# USB3_2_Type_A.net
KiCad netlist of a schematic drawn in Altium Designer
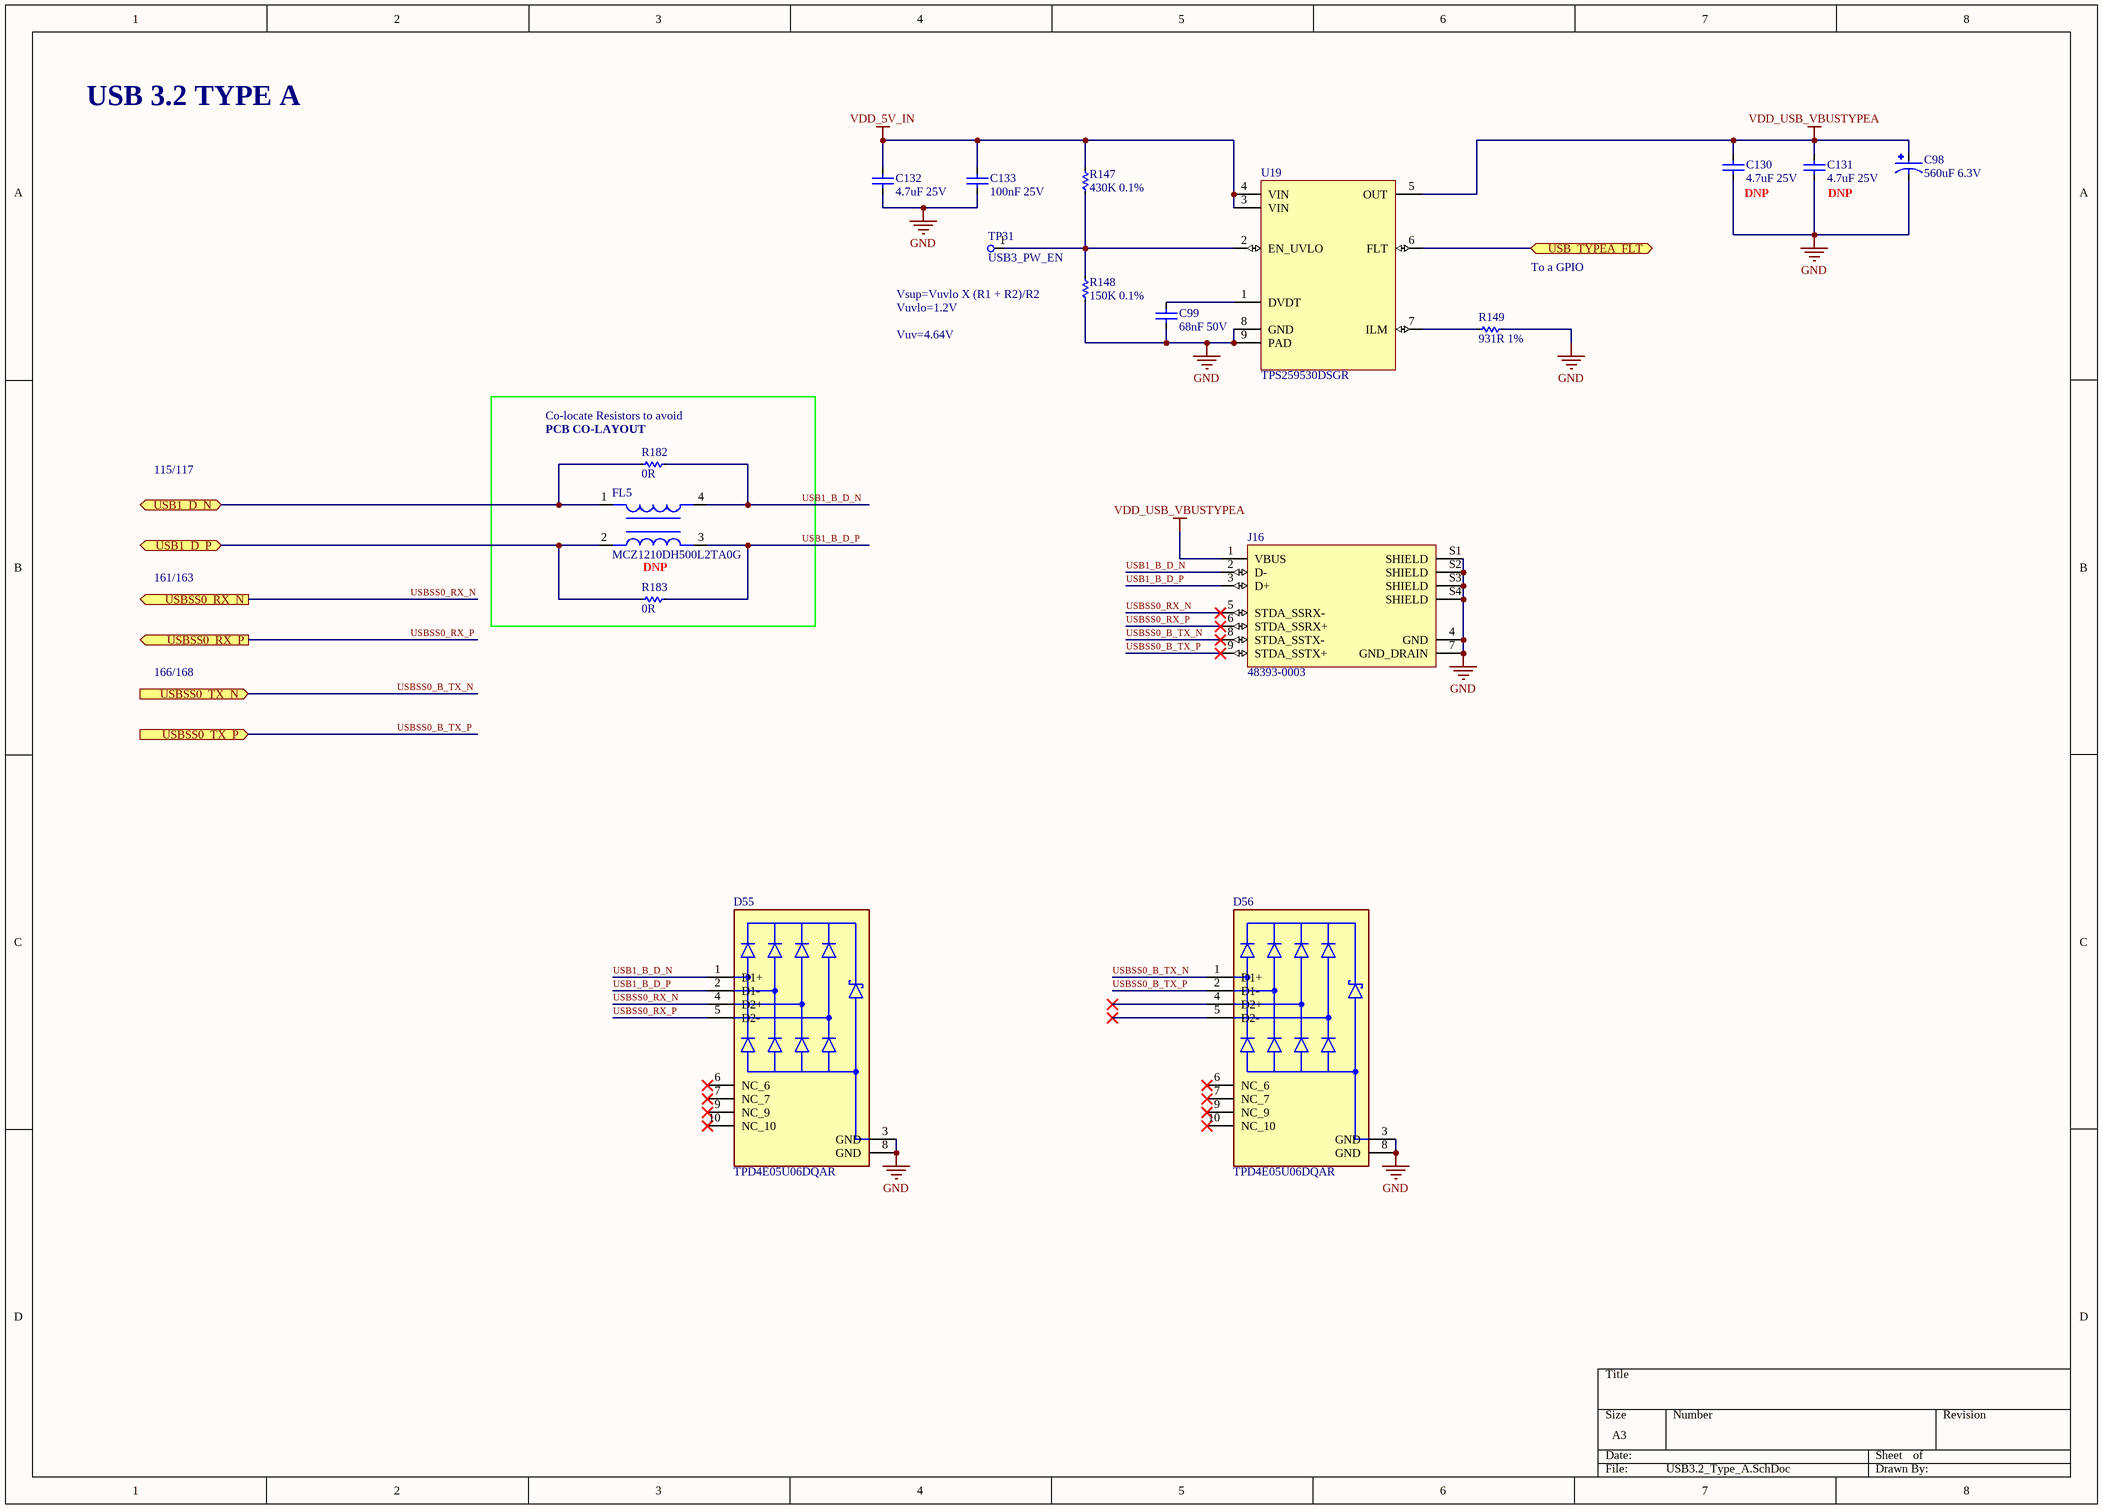
[diagram p0: USB3.2_Type_A.SchDoc]

(export (version "E")
  (design (tool "Eeschema 10.0.6"))
  (components
    (comp (ref "C98")
      (value "560uF 6.3V")
      (footprint "CP_ELEC_8X7.7")
      (description "Cap Aluminum Polymer 560uF 6.3VDC 20% (8 X 7.7mm) SMD 0.009 Ohm 4500mA 2000h 105C T/R")
      (fields
        (field (name "MANUFACTURER") "Nichicon")
        (field (name "MANUFACTURER PART NUMBER") "RHA0J561MCN1GS")
      )
      (libsource (lib "GM_Altium_Library") (part "RHA0J561MCN1GS"))
    )
    (comp (ref "C99")
      (value "68nF 50V")
      (footprint "C0805")
      (description "Cap Cer 0805 68NF 50V X7R 10%")
      (fields
        (field (name "MANUFACTURER") "KEMET")
        (field (name "MANUFACTURER PART NUMBER") "C0805C683K5RECAUTO7210")
      )
      (libsource (lib "GM_Altium_Library") (part "C0805C683K5RECAUTO7210"))
    )
    (comp (ref "C130")
      (value "4.7uF 25V")
      (footprint "C0603")
      (description "0603 4.7 uF 25 V ±10 % Tolerance X5R SMT Multilayer Ceramic Capacitor")
      (fields
        (field (name "MANUFACTURER") "Murata")
        (field (name "MANUFACTURER PART NUMBER") "GRM188R61E475KE11D")
      )
      (libsource (lib "GM_Altium_Library") (part "GRM188R61E475KE11D"))
    )
    (comp (ref "C131")
      (value "4.7uF 25V")
      (footprint "C0603")
      (description "0603 4.7 uF 25 V ±10 % Tolerance X5R SMT Multilayer Ceramic Capacitor")
      (fields
        (field (name "MANUFACTURER") "Murata")
        (field (name "MANUFACTURER PART NUMBER") "GRM188R61E475KE11D")
      )
      (libsource (lib "GM_Altium_Library") (part "GRM188R61E475KE11D"))
    )
    (comp (ref "C132")
      (value "4.7uF 25V")
      (footprint "C0603")
      (description "0603 4.7 uF 25 V ±10 % Tolerance X5R SMT Multilayer Ceramic Capacitor")
      (fields
        (field (name "MANUFACTURER") "Murata")
        (field (name "MANUFACTURER PART NUMBER") "GRM188R61E475KE11D")
      )
      (libsource (lib "GM_Altium_Library") (part "GRM188R61E475KE11D"))
    )
    (comp (ref "C133")
      (value "100nF 25V")
      (footprint "C0402")
      (description "CAP CER 0.1UF 25V X5R 0402 / High Value Multilayer Ceramic Capacitors (High dielectric type)")
      (fields
        (field (name "MANUFACTURER") "Taiyo Yuden")
        (field (name "MANUFACTURER PART NUMBER") "TMK105BJ104KV-F")
      )
      (libsource (lib "GM_Altium_Library") (part "TMK105BJ104KV-F"))
    )
    (comp (ref "D55")
      (value "TPD4E05U06DQAR")
      (footprint "TPD4E05U06DQAR")
      (description "Quad 0.5-pF, 5.5-V, ±12-kV ESD protection diode for USB, HDMI & High Speed Interfaces")
      (fields (field (name "MANUFACTURER") "Texas Instruments"))
      (libsource (lib "GM_Altium_Library") (part "TPD4E05U06DQAR"))
    )
    (comp (ref "D56")
      (value "TPD4E05U06DQAR")
      (footprint "TPD4E05U06DQAR")
      (description "Quad 0.5-pF, 5.5-V, ±12-kV ESD protection diode for USB, HDMI & High Speed Interfaces")
      (fields (field (name "MANUFACTURER") "Texas Instruments"))
      (libsource (lib "GM_Altium_Library") (part "TPD4E05U06DQAR"))
    )
    (comp (ref "FL5")
      (value "MCZ1210DH500L2TA0G")
      (footprint "MCZ1210DH500L2TA0G")
      (description "2 Line Common Mode Choke Surface Mount 50 Ohms 100mA DCR 2.5Ohm")
      (fields (field (name "MANUFACTURER") "TDK"))
      (libsource (lib "GM_Altium_Library") (part "MCZ1210DH500L2TA0G"))
    )
    (comp (ref "J16")
      (value "48393-0003")
      (footprint "0483930003")
      (description "Conn USB Type A F 9 POS 2mm/2.5mm Solder RA Thru-Hole 9 Terminal 1 Port Embossed T/R")
      (fields (field (name "MANUFACTURER") "Molex"))
      (libsource (lib "GM_Altium_Library") (part "48393-0003"))
    )
    (comp (ref "R147")
      (value "430K 0.1%")
      (footprint "R0603")
      (description "Res Thin Film 0603 430K Ohm 0.1% 1/16W ±25ppm/°C Molded SMD SMD Paper T/R")
      (fields
        (field (name "MANUFACTURER") "TE Connectivity")
        (field (name "MANUFACTURER PART NUMBER") "CPF0603B430KE1")
      )
      (libsource (lib "GM_Altium_Library") (part "CPF0603B430KE1"))
    )
    (comp (ref "R148")
      (value "150K 0.1%")
      (footprint "R0402")
      (description "Res Thin Film 0402 150K Ohm 0.1% 1/16W ±25ppm/°C Molded SMD")
      (fields
        (field (name "MANUFACTURER") "Yageo")
        (field (name "MANUFACTURER PART NUMBER") "RT0402BRD07150KL")
      )
      (libsource (lib "GM_Altium_Library") (part "RT0402BRD07150KL"))
    )
    (comp (ref "R149")
      (value "931R 1%")
      (footprint "R0402")
      (description "Res Thick Film 0402 931 Ohm 1% 1/16W ±100ppm/°C Molded SMD Paper T/R")
      (fields
        (field (name "MANUFACTURER") "Yageo")
        (field (name "MANUFACTURER PART NUMBER") "RC0402FR-07931RL")
      )
      (libsource (lib "GM_Altium_Library") (part "RC0402FR-07931RL"))
    )
    (comp (ref "R182")
      (value "0R")
      (footprint "R0402")
      (description "Res Jumper Thick Film 0402 0 Ohm 5% 1/16W Molded SMD Paper T/R")
      (fields
        (field (name "MANUFACTURER") "Yageo")
        (field (name "MANUFACTURER PART NUMBER") "RC0402JR-070RP")
      )
      (libsource (lib "GM_Altium_Library") (part "RC0402JR-070RP"))
    )
    (comp (ref "R183")
      (value "0R")
      (footprint "R0402")
      (description "Res Jumper Thick Film 0402 0 Ohm 5% 1/16W Molded SMD Paper T/R")
      (fields
        (field (name "MANUFACTURER") "Yageo")
        (field (name "MANUFACTURER PART NUMBER") "RC0402JR-070RP")
      )
      (libsource (lib "GM_Altium_Library") (part "RC0402JR-070RP"))
    )
    (comp (ref "TP31")
      (value "USB3_PW_EN")
      (footprint "TestPoint_Pad_D1.0mm")
      (libsource (lib "GM_Altium_Library") (part "TestPoint_D1mm"))
    )
    (comp (ref "U19")
      (value "TPS259530DSGR")
      (footprint "WSON(2X2)-8")
      (description "TPS259530 12V eFuse with Fast Overvoltage Protection 2.7V to 18V 4A 34m Ohm 8-Pin WSON T/R")
      (fields (field (name "MANUFACTURER") "Texas Instruments"))
      (libsource (lib "GM_Altium_Library") (part "TPS259530DSGR"))
    )
  )
  (nets
    (net (code "1") (name "/USB1_B_D_N") (class "Default")
      (node (ref "D55") (pin "1") (pinfunction "D1+_1") (pintype "passive"))
      (node (ref "FL5") (pin "4") (pinfunction "4_4") (pintype "passive"))
      (node (ref "J16") (pin "2") (pinfunction "D-_2") (pintype "bidirectional"))
      (node (ref "R182") (pin "2") (pinfunction "2_2") (pintype "passive"))
    )
    (net (code "2") (name "/USB1_B_D_P") (class "Default")
      (node (ref "D55") (pin "2") (pinfunction "D1-_2") (pintype "passive"))
      (node (ref "FL5") (pin "3") (pinfunction "3_3") (pintype "passive"))
      (node (ref "J16") (pin "3") (pinfunction "D+_3") (pintype "bidirectional"))
      (node (ref "R183") (pin "2") (pinfunction "2_2") (pintype "passive"))
    )
    (net (code "3") (name "/USB1_D_N") (class "Default")
      (node (ref "FL5") (pin "1") (pinfunction "1_1") (pintype "passive"))
      (node (ref "R182") (pin "1") (pinfunction "1_1") (pintype "passive"))
    )
    (net (code "4") (name "/USB1_D_P") (class "Default")
      (node (ref "FL5") (pin "2") (pinfunction "2_2") (pintype "passive"))
      (node (ref "R183") (pin "1") (pinfunction "1_1") (pintype "passive"))
    )
    (net (code "5") (name "/USBSS0_B_TX_N") (class "Default")
      (node (ref "D56") (pin "1") (pinfunction "D1+_1") (pintype "passive"))
      (node (ref "J16") (pin "8") (pinfunction "STDA_SSTX-_8") (pintype "bidirectional"))
    )
    (net (code "6") (name "/USBSS0_B_TX_P") (class "Default")
      (node (ref "D56") (pin "2") (pinfunction "D1-_2") (pintype "passive"))
      (node (ref "J16") (pin "9") (pinfunction "STDA_SSTX+_9") (pintype "bidirectional"))
    )
    (net (code "7") (name "/USBSS0_RX_N") (class "Default")
      (node (ref "D55") (pin "4") (pinfunction "D2+_4") (pintype "passive"))
      (node (ref "J16") (pin "5") (pinfunction "STDA_SSRX-_5") (pintype "bidirectional"))
    )
    (net (code "8") (name "/USBSS0_RX_P") (class "Default")
      (node (ref "D55") (pin "5") (pinfunction "D2-_5") (pintype "passive"))
      (node (ref "J16") (pin "6") (pinfunction "STDA_SSRX+_6") (pintype "bidirectional"))
    )
    (net (code "9") (name "/USB_TYPEA_FLT") (class "Default")
      (node (ref "U19") (pin "6") (pinfunction "FLT_6") (pintype "bidirectional"))
    )
    (net (code "10") (name "GND") (class "Default")
      (node (ref "C130") (pin "1") (pinfunction "1_1") (pintype "passive"))
      (node (ref "C131") (pin "1") (pinfunction "1_1") (pintype "passive"))
      (node (ref "C132") (pin "1") (pinfunction "1_1") (pintype "passive"))
      (node (ref "C133") (pin "1") (pinfunction "1_1") (pintype "passive"))
      (node (ref "C98") (pin "2") (pinfunction "C_2") (pintype "passive"))
      (node (ref "C99") (pin "1") (pinfunction "1_1") (pintype "passive"))
      (node (ref "D55") (pin "3") (pinfunction "GND_3") (pintype "power_in"))
      (node (ref "D55") (pin "8") (pinfunction "GND_8") (pintype "power_in"))
      (node (ref "D56") (pin "3") (pinfunction "GND_3") (pintype "power_in"))
      (node (ref "D56") (pin "8") (pinfunction "GND_8") (pintype "power_in"))
      (node (ref "J16") (pin "4") (pinfunction "GND_4") (pintype "power_in"))
      (node (ref "J16") (pin "7") (pinfunction "GND_DRAIN_7") (pintype "power_in"))
      (node (ref "J16") (pin "S1") (pinfunction "SHIELD_S1") (pintype "passive"))
      (node (ref "J16") (pin "S2") (pinfunction "SHIELD_S2") (pintype "passive"))
      (node (ref "J16") (pin "S3") (pinfunction "SHIELD_S3") (pintype "passive"))
      (node (ref "J16") (pin "S4") (pinfunction "SHIELD_S4") (pintype "passive"))
      (node (ref "R148") (pin "1") (pinfunction "1_1") (pintype "passive"))
      (node (ref "R149") (pin "2") (pinfunction "2_2") (pintype "passive"))
      (node (ref "U19") (pin "8") (pinfunction "GND_8") (pintype "power_in"))
      (node (ref "U19") (pin "9") (pinfunction "PAD_9") (pintype "power_in"))
    )
    (net (code "11") (name "Net-(U19-DVDT)") (class "Default")
      (node (ref "C99") (pin "2") (pinfunction "2_2") (pintype "passive"))
      (node (ref "U19") (pin "1") (pinfunction "DVDT_1") (pintype "passive"))
    )
    (net (code "12") (name "Net-(U19-EN_UVLO)") (class "Default")
      (node (ref "R147") (pin "1") (pinfunction "1_1") (pintype "passive"))
      (node (ref "R148") (pin "2") (pinfunction "2_2") (pintype "passive"))
      (node (ref "TP31") (pin "1") (pinfunction "1_1") (pintype "passive"))
      (node (ref "U19") (pin "2") (pinfunction "EN_UVLO_2") (pintype "bidirectional"))
    )
    (net (code "13") (name "Net-(U19-ILM)") (class "Default")
      (node (ref "R149") (pin "1") (pinfunction "1_1") (pintype "passive"))
      (node (ref "U19") (pin "7") (pinfunction "ILM_7") (pintype "bidirectional"))
    )
    (net (code "14") (name "VDD_5V_IN") (class "Default")
      (node (ref "C132") (pin "2") (pinfunction "2_2") (pintype "passive"))
      (node (ref "C133") (pin "2") (pinfunction "2_2") (pintype "passive"))
      (node (ref "R147") (pin "2") (pinfunction "2_2") (pintype "passive"))
      (node (ref "U19") (pin "3") (pinfunction "VIN_3") (pintype "power_in"))
      (node (ref "U19") (pin "4") (pinfunction "VIN_4") (pintype "power_in"))
    )
    (net (code "15") (name "VDD_USB_VBUSTYPEA") (class "Default")
      (node (ref "C130") (pin "2") (pinfunction "2_2") (pintype "passive"))
      (node (ref "C131") (pin "2") (pinfunction "2_2") (pintype "passive"))
      (node (ref "C98") (pin "1") (pinfunction "A_1") (pintype "passive"))
      (node (ref "J16") (pin "1") (pinfunction "VBUS_1") (pintype "power_in"))
      (node (ref "U19") (pin "5") (pinfunction "OUT_5") (pintype "power_in"))
    )
    (net (code "16") (name "unconnected-(D55-NC_6-Pad6)") (class "Default")
      (node (ref "D55") (pin "6") (pinfunction "NC_6_6") (pintype "passive+no_connect"))
    )
    (net (code "17") (name "unconnected-(D55-NC_7-Pad7)") (class "Default")
      (node (ref "D55") (pin "7") (pinfunction "NC_7_7") (pintype "passive+no_connect"))
    )
    (net (code "18") (name "unconnected-(D55-NC_9-Pad9)") (class "Default")
      (node (ref "D55") (pin "9") (pinfunction "NC_9_9") (pintype "passive+no_connect"))
    )
    (net (code "19") (name "unconnected-(D55-NC_10-Pad10)") (class "Default")
      (node (ref "D55") (pin "10") (pinfunction "NC_10_10") (pintype "passive+no_connect"))
    )
    (net (code "20") (name "unconnected-(D56-D2+-Pad4)") (class "Default")
      (node (ref "D56") (pin "4") (pinfunction "D2+_4") (pintype "passive+no_connect"))
    )
    (net (code "21") (name "unconnected-(D56-D2--Pad5)") (class "Default")
      (node (ref "D56") (pin "5") (pinfunction "D2-_5") (pintype "passive+no_connect"))
    )
    (net (code "22") (name "unconnected-(D56-NC_6-Pad6)") (class "Default")
      (node (ref "D56") (pin "6") (pinfunction "NC_6_6") (pintype "passive+no_connect"))
    )
    (net (code "23") (name "unconnected-(D56-NC_7-Pad7)") (class "Default")
      (node (ref "D56") (pin "7") (pinfunction "NC_7_7") (pintype "passive+no_connect"))
    )
    (net (code "24") (name "unconnected-(D56-NC_9-Pad9)") (class "Default")
      (node (ref "D56") (pin "9") (pinfunction "NC_9_9") (pintype "passive+no_connect"))
    )
    (net (code "25") (name "unconnected-(D56-NC_10-Pad10)") (class "Default")
      (node (ref "D56") (pin "10") (pinfunction "NC_10_10") (pintype "passive+no_connect"))
    )
  )
)
